# ce2.net
KiCad netlist of a schematic drawn in EAGLE
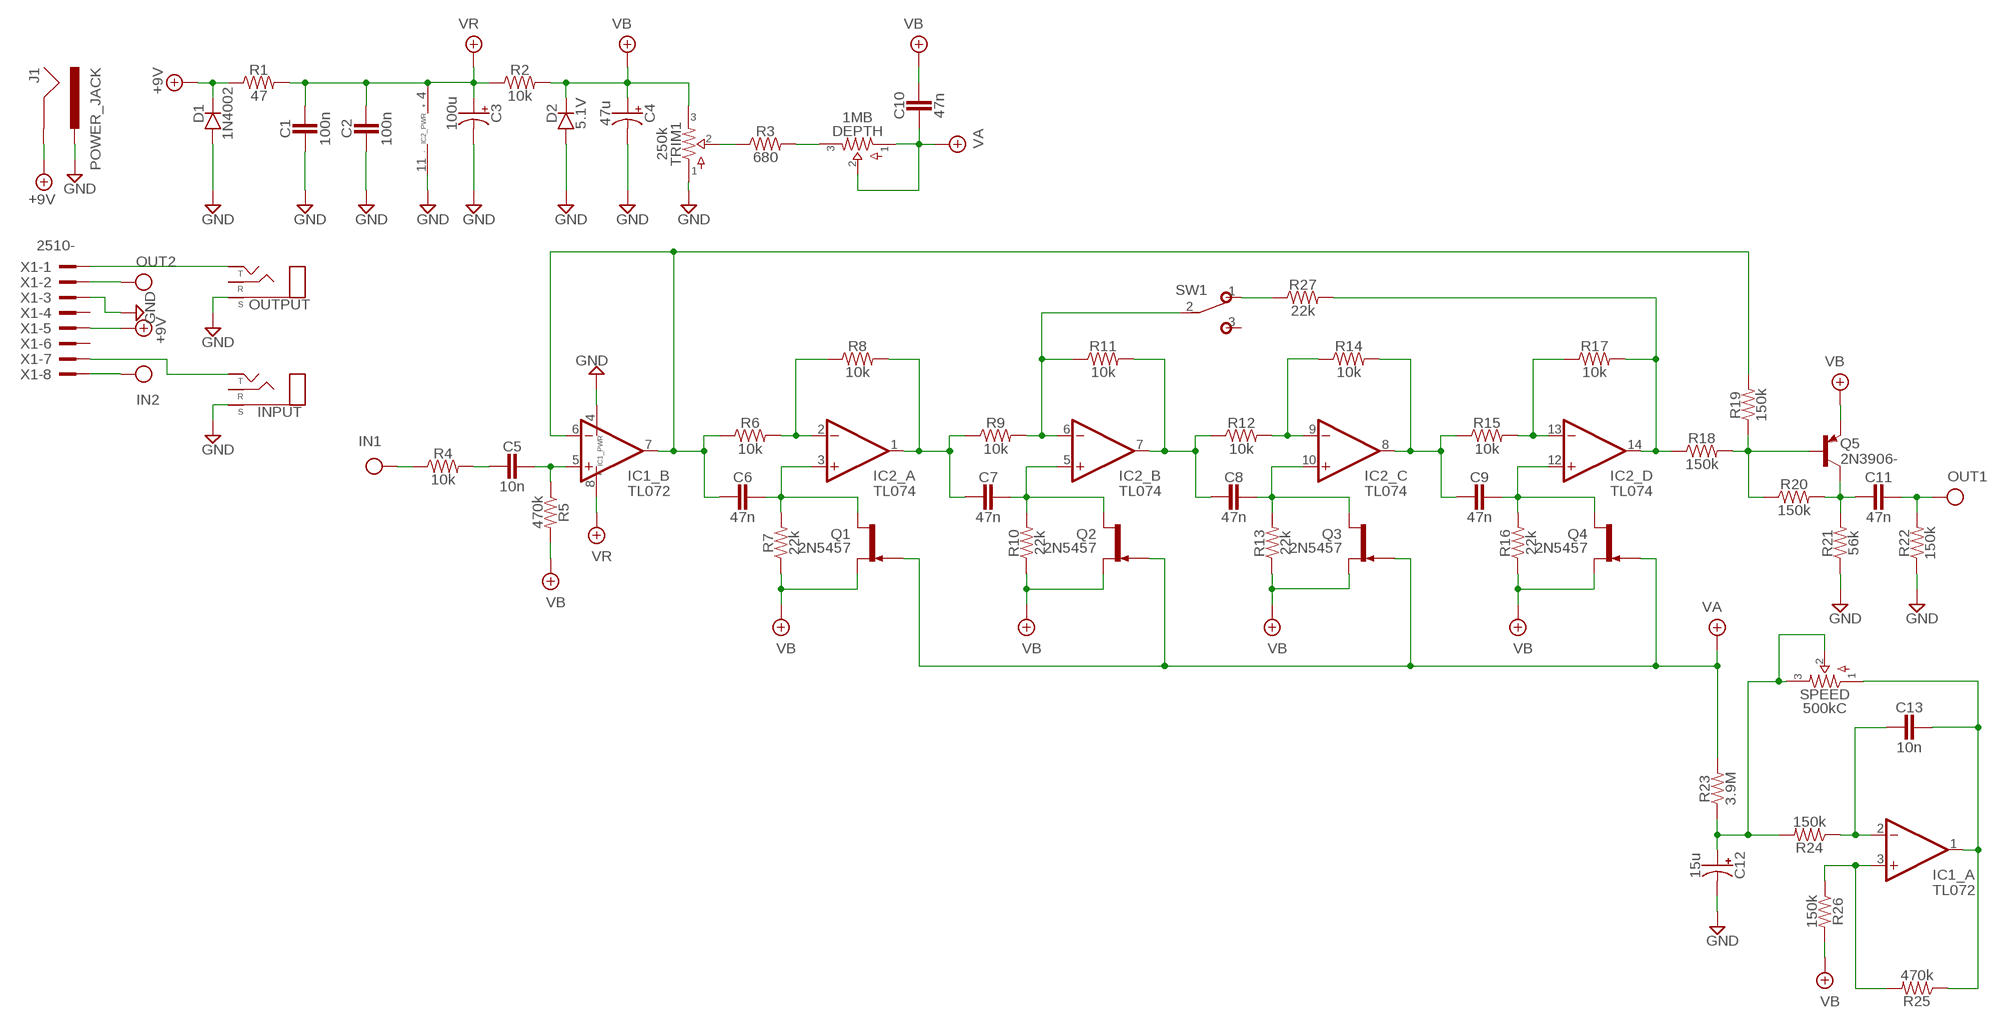
[diagram p0: schematic, sheet 1]

(export (version "E")
  (design (tool "Eeschema 10.0.6"))
  (components
    (comp (ref "C1")
      (value "100n")
      (footprint "eagle-import:050X030_025_2")
      (libsource (lib "eagle-import") (part "CER/FILM2"))
    )
    (comp (ref "C2")
      (value "100n")
      (footprint "eagle-import:050X030_025_2")
      (libsource (lib "eagle-import") (part "CER/FILM2"))
    )
    (comp (ref "C3")
      (value "100u")
      (footprint "eagle-import:050_020")
      (libsource (lib "eagle-import") (part "0500"))
    )
    (comp (ref "C4")
      (value "47u")
      (footprint "eagle-import:050_020")
      (libsource (lib "eagle-import") (part "0500"))
    )
    (comp (ref "C5")
      (value "10n")
      (footprint "eagle-import:BOX_SMALL")
      (libsource (lib "eagle-import") (part "CER/FILMBOX.1"))
    )
    (comp (ref "C6")
      (value "47n")
      (footprint "eagle-import:BOX_SMALL")
      (libsource (lib "eagle-import") (part "CER/FILMBOX.1"))
    )
    (comp (ref "C7")
      (value "47n")
      (footprint "eagle-import:BOX_SMALL")
      (libsource (lib "eagle-import") (part "CER/FILMBOX.1"))
    )
    (comp (ref "C8")
      (value "47n")
      (footprint "eagle-import:BOX_SMALL")
      (libsource (lib "eagle-import") (part "CER/FILMBOX.1"))
    )
    (comp (ref "C9")
      (value "47n")
      (footprint "eagle-import:BOX_SMALL")
      (libsource (lib "eagle-import") (part "CER/FILMBOX.1"))
    )
    (comp (ref "C10")
      (value "47n")
      (footprint "eagle-import:BOX_SMALL")
      (libsource (lib "eagle-import") (part "CER/FILMBOX.1"))
    )
    (comp (ref "C11")
      (value "47n")
      (footprint "eagle-import:BOX_SMALL")
      (libsource (lib "eagle-import") (part "CER/FILMBOX.1"))
    )
    (comp (ref "C12")
      (value "15u")
      (footprint "eagle-import:050_020_1")
      (libsource (lib "eagle-import") (part "0501"))
    )
    (comp (ref "C13")
      (value "10n")
      (footprint "eagle-import:BOX_SMALL")
      (libsource (lib "eagle-import") (part "CER/FILMBOX.1"))
    )
    (comp (ref "D1")
      (value "1N4002")
      (footprint "eagle-import:DO41-2")
      (libsource (lib "eagle-import") (part "DO41.2"))
    )
    (comp (ref "D2")
      (value "5.1V")
      (footprint "eagle-import:DO41-2")
      (libsource (lib "eagle-import") (part "DO41.2"))
    )
    (comp (ref "DEPTH")
      (value "1MB")
      (footprint "eagle-import:16MM")
      (libsource (lib "eagle-import") (part "POTS16MM"))
    )
    (comp (ref "IC1")
      (value "TL072")
      (footprint "eagle-import:DIL0")
      (libsource (lib "eagle-import") (part "DUALTH"))
    )
    (comp (ref "IC2")
      (value "TL074")
      (footprint "eagle-import:DIL14")
      (libsource (lib "eagle-import") (part "QUADTH"))
    )
    (comp (ref "INPUT")
      (value "STEREONMJ")
      (footprint "eagle-import:NMJ6HCD2")
      (libsource (lib "eagle-import") (part "STEREONMJ"))
    )
    (comp (ref "J1")
      (value "POWER_JACK")
      (footprint "eagle-import:POWER_JACK_PTH")
      (libsource (lib "eagle-import") (part "POWER_JACK"))
    )
    (comp (ref "OUTPUT")
      (value "STEREONMJ")
      (footprint "eagle-import:NMJ6HCD2")
      (libsource (lib "eagle-import") (part "STEREONMJ"))
    )
    (comp (ref "Q1")
      (value "2N5457")
      (footprint "eagle-import:TO92-")
      (libsource (lib "eagle-import") (part "2N5457"))
    )
    (comp (ref "Q2")
      (value "2N5457")
      (footprint "eagle-import:TO92-")
      (libsource (lib "eagle-import") (part "2N5457"))
    )
    (comp (ref "Q3")
      (value "2N5457")
      (footprint "eagle-import:TO92-")
      (libsource (lib "eagle-import") (part "2N5457"))
    )
    (comp (ref "Q4")
      (value "2N5457")
      (footprint "eagle-import:TO92-")
      (libsource (lib "eagle-import") (part "2N5457"))
    )
    (comp (ref "Q5")
      (value "2N3906-")
      (footprint "eagle-import:TO92-")
      (libsource (lib "eagle-import") (part "2N3906-"))
    )
    (comp (ref "R1")
      (value "47")
      (footprint "eagle-import:R0207_3")
      (libsource (lib "eagle-import") (part "R_.3B"))
    )
    (comp (ref "R2")
      (value "10k")
      (footprint "eagle-import:R0207_3")
      (libsource (lib "eagle-import") (part "R_.3B"))
    )
    (comp (ref "R3")
      (value "680")
      (footprint "eagle-import:R0207_3")
      (libsource (lib "eagle-import") (part "R_.3B"))
    )
    (comp (ref "R4")
      (value "10k")
      (footprint "eagle-import:R0207_3")
      (libsource (lib "eagle-import") (part "R_.3B"))
    )
    (comp (ref "R5")
      (value "470k")
      (footprint "eagle-import:R0207_3")
      (libsource (lib "eagle-import") (part "R_.3B"))
    )
    (comp (ref "R6")
      (value "10k")
      (footprint "eagle-import:R0207_3")
      (libsource (lib "eagle-import") (part "R_.3B"))
    )
    (comp (ref "R7")
      (value "22k")
      (footprint "eagle-import:R0207_3")
      (libsource (lib "eagle-import") (part "R_.3B"))
    )
    (comp (ref "R8")
      (value "10k")
      (footprint "eagle-import:R0207_3")
      (libsource (lib "eagle-import") (part "R_.3B"))
    )
    (comp (ref "R9")
      (value "10k")
      (footprint "eagle-import:R0207_3")
      (libsource (lib "eagle-import") (part "R_.3B"))
    )
    (comp (ref "R10")
      (value "22k")
      (footprint "eagle-import:R0207_3")
      (libsource (lib "eagle-import") (part "R_.3B"))
    )
    (comp (ref "R11")
      (value "10k")
      (footprint "eagle-import:R0207_3")
      (libsource (lib "eagle-import") (part "R_.3B"))
    )
    (comp (ref "R12")
      (value "10k")
      (footprint "eagle-import:R0207_3")
      (libsource (lib "eagle-import") (part "R_.3B"))
    )
    (comp (ref "R13")
      (value "22k")
      (footprint "eagle-import:R0207_3")
      (libsource (lib "eagle-import") (part "R_.3B"))
    )
    (comp (ref "R14")
      (value "10k")
      (footprint "eagle-import:R0207_3")
      (libsource (lib "eagle-import") (part "R_.3B"))
    )
    (comp (ref "R15")
      (value "10k")
      (footprint "eagle-import:R0207_3")
      (libsource (lib "eagle-import") (part "R_.3B"))
    )
    (comp (ref "R16")
      (value "22k")
      (footprint "eagle-import:R0207_3")
      (libsource (lib "eagle-import") (part "R_.3B"))
    )
    (comp (ref "R17")
      (value "10k")
      (footprint "eagle-import:R0207_3")
      (libsource (lib "eagle-import") (part "R_.3B"))
    )
    (comp (ref "R18")
      (value "150k")
      (footprint "eagle-import:R0207_3")
      (libsource (lib "eagle-import") (part "R_.3B"))
    )
    (comp (ref "R19")
      (value "150k")
      (footprint "eagle-import:R0207_3")
      (libsource (lib "eagle-import") (part "R_.3B"))
    )
    (comp (ref "R20")
      (value "150k")
      (footprint "eagle-import:R0207_3")
      (libsource (lib "eagle-import") (part "R_.3B"))
    )
    (comp (ref "R21")
      (value "56k")
      (footprint "eagle-import:R0207_3")
      (libsource (lib "eagle-import") (part "R_.3B"))
    )
    (comp (ref "R22")
      (value "150k")
      (footprint "eagle-import:R0207_3")
      (libsource (lib "eagle-import") (part "R_.3B"))
    )
    (comp (ref "R23")
      (value "3.9M")
      (footprint "eagle-import:R0207_3")
      (libsource (lib "eagle-import") (part "R_.3B"))
    )
    (comp (ref "R24")
      (value "150k")
      (footprint "eagle-import:R0207_3")
      (libsource (lib "eagle-import") (part "R_.3B"))
    )
    (comp (ref "R25")
      (value "470k")
      (footprint "eagle-import:R0207_3")
      (libsource (lib "eagle-import") (part "R_.3B"))
    )
    (comp (ref "R26")
      (value "150k")
      (footprint "eagle-import:R0207_3")
      (libsource (lib "eagle-import") (part "R_.3B"))
    )
    (comp (ref "R27")
      (value "22k")
      (footprint "eagle-import:R0207_3")
      (libsource (lib "eagle-import") (part "R_.3B"))
    )
    (comp (ref "SPEED")
      (value "500kC")
      (footprint "eagle-import:16MM")
      (libsource (lib "eagle-import") (part "POTS16MM"))
    )
    (comp (ref "SW1")
      (value "SPDTPIN_MOUNT")
      (footprint "eagle-import:1MS1T1B1C0M2QE")
      (libsource (lib "eagle-import") (part "SPDTPIN_MOUNT"))
    )
    (comp (ref "TRIM1")
      (value "250k")
      (footprint "eagle-import:RTRIM3296W")
      (libsource (lib "eagle-import") (part "POTSTEST"))
    )
    (comp (ref "X1")
      (value "2510-")
      (footprint "eagle-import:PAK100_2500-10")
      (fields (field (name "MF") "3M") (field (name "MPN") "2510-6002UB"))
      (libsource (lib "eagle-import") (part "2510-"))
    )
  )
  (nets
    (net (code "1") (name "+9V") (class "Default")
      (node (ref "D1") (pin "C") (pinfunction "C_C") (pintype "passive"))
      (node (ref "J1") (pin "GND") (pinfunction "GND_GND") (pintype "bidirectional"))
      (node (ref "R1") (pin "1") (pinfunction "1_1") (pintype "passive"))
      (node (ref "X1") (pin "5") (pinfunction "KL_5") (pintype "passive"))
    )
    (net (code "2") (name "GND") (class "Default")
      (node (ref "C1") (pin "2") (pinfunction "2_2") (pintype "passive"))
      (node (ref "C12") (pin "-") (pinfunction "-_-") (pintype "passive"))
      (node (ref "C2") (pin "2") (pinfunction "2_2") (pintype "passive"))
      (node (ref "C3") (pin "-") (pinfunction "-_-") (pintype "passive"))
      (node (ref "C4") (pin "-") (pinfunction "-_-") (pintype "passive"))
      (node (ref "D1") (pin "A") (pinfunction "A_A") (pintype "passive"))
      (node (ref "D2") (pin "A") (pinfunction "A_A") (pintype "passive"))
      (node (ref "IC1") (pin "4") (pinfunction "V-_4") (pintype "power_in"))
      (node (ref "IC2") (pin "11") (pinfunction "V-_11") (pintype "power_in"))
      (node (ref "INPUT") (pin "S") (pinfunction "S_S") (pintype "passive"))
      (node (ref "J1") (pin "PWR") (pinfunction "PWR_PWR") (pintype "bidirectional"))
      (node (ref "OUTPUT") (pin "S") (pinfunction "S_S") (pintype "passive"))
      (node (ref "R21") (pin "1") (pinfunction "1_1") (pintype "passive"))
      (node (ref "R22") (pin "1") (pinfunction "1_1") (pintype "passive"))
      (node (ref "TRIM1") (pin "1") (pinfunction "1_1") (pintype "passive"))
      (node (ref "X1") (pin "3") (pinfunction "KL_3") (pintype "passive"))
    )
    (net (code "3") (name "IN") (class "Default")
      (node (ref "R4") (pin "1") (pinfunction "1_1") (pintype "passive"))
      (node (ref "X1") (pin "8") (pinfunction "KL_8") (pintype "passive"))
    )
    (net (code "4") (name "Net-(C5-Pad2)") (class "Default")
      (node (ref "C5") (pin "2") (pinfunction "2_2") (pintype "passive"))
      (node (ref "R4") (pin "2") (pinfunction "2_2") (pintype "passive"))
    )
    (net (code "5") (name "Net-(C12-Pad+)") (class "Default")
      (node (ref "C12") (pin "+") (pinfunction "+_+") (pintype "passive"))
      (node (ref "R23") (pin "1") (pinfunction "1_1") (pintype "passive"))
      (node (ref "R24") (pin "2") (pinfunction "2_2") (pintype "passive"))
      (node (ref "SPEED") (pin "2") (pinfunction "2_2") (pintype "passive"))
      (node (ref "SPEED") (pin "3") (pinfunction "3_3") (pintype "passive"))
    )
    (net (code "6") (name "Net-(DEPTH-Pad3)") (class "Default")
      (node (ref "DEPTH") (pin "3") (pinfunction "3_3") (pintype "passive"))
      (node (ref "R3") (pin "2") (pinfunction "2_2") (pintype "passive"))
    )
    (net (code "7") (name "Net-(IC1A-+IN)") (class "Default")
      (node (ref "IC1") (pin "3") (pinfunction "+IN_3") (pintype "input"))
      (node (ref "R25") (pin "2") (pinfunction "2_2") (pintype "passive"))
      (node (ref "R26") (pin "1") (pinfunction "1_1") (pintype "passive"))
    )
    (net (code "8") (name "Net-(IC1A--IN)") (class "Default")
      (node (ref "C13") (pin "2") (pinfunction "2_2") (pintype "passive"))
      (node (ref "IC1") (pin "2") (pinfunction "-IN_2") (pintype "input"))
      (node (ref "R24") (pin "1") (pinfunction "1_1") (pintype "passive"))
    )
    (net (code "9") (name "Net-(IC1A-OUT)") (class "Default")
      (node (ref "C13") (pin "1") (pinfunction "1_1") (pintype "passive"))
      (node (ref "IC1") (pin "1") (pinfunction "OUT_1") (pintype "output"))
      (node (ref "R25") (pin "1") (pinfunction "1_1") (pintype "passive"))
      (node (ref "SPEED") (pin "1") (pinfunction "1_1") (pintype "passive"))
    )
    (net (code "10") (name "Net-(IC1B-+IN)") (class "Default")
      (node (ref "C5") (pin "1") (pinfunction "1_1") (pintype "passive"))
      (node (ref "IC1") (pin "5") (pinfunction "+IN_5") (pintype "input"))
      (node (ref "R5") (pin "1") (pinfunction "1_1") (pintype "passive"))
    )
    (net (code "11") (name "Net-(IC1B--IN)") (class "Default")
      (node (ref "C6") (pin "2") (pinfunction "2_2") (pintype "passive"))
      (node (ref "IC1") (pin "6") (pinfunction "-IN_6") (pintype "input"))
      (node (ref "IC1") (pin "7") (pinfunction "OUT_7") (pintype "output"))
      (node (ref "R19") (pin "2") (pinfunction "2_2") (pintype "passive"))
      (node (ref "R6") (pin "1") (pinfunction "1_1") (pintype "passive"))
    )
    (net (code "12") (name "Net-(IC2A-+IN)") (class "Default")
      (node (ref "C6") (pin "1") (pinfunction "1_1") (pintype "passive"))
      (node (ref "IC2") (pin "3") (pinfunction "+IN_3") (pintype "input"))
      (node (ref "Q1") (pin "3") (pinfunction "D_3") (pintype "passive"))
      (node (ref "R7") (pin "2") (pinfunction "2_2") (pintype "passive"))
    )
    (net (code "13") (name "Net-(IC2A--IN)") (class "Default")
      (node (ref "IC2") (pin "2") (pinfunction "-IN_2") (pintype "input"))
      (node (ref "R6") (pin "2") (pinfunction "2_2") (pintype "passive"))
      (node (ref "R8") (pin "1") (pinfunction "1_1") (pintype "passive"))
    )
    (net (code "14") (name "Net-(IC2A-OUT)") (class "Default")
      (node (ref "C7") (pin "2") (pinfunction "2_2") (pintype "passive"))
      (node (ref "IC2") (pin "1") (pinfunction "OUT_1") (pintype "output"))
      (node (ref "R8") (pin "2") (pinfunction "2_2") (pintype "passive"))
      (node (ref "R9") (pin "1") (pinfunction "1_1") (pintype "passive"))
    )
    (net (code "15") (name "Net-(IC2B-+IN)") (class "Default")
      (node (ref "C7") (pin "1") (pinfunction "1_1") (pintype "passive"))
      (node (ref "IC2") (pin "5") (pinfunction "+IN_5") (pintype "input"))
      (node (ref "Q2") (pin "3") (pinfunction "D_3") (pintype "passive"))
      (node (ref "R10") (pin "2") (pinfunction "2_2") (pintype "passive"))
    )
    (net (code "16") (name "Net-(IC2B--IN)") (class "Default")
      (node (ref "IC2") (pin "6") (pinfunction "-IN_6") (pintype "input"))
      (node (ref "R11") (pin "1") (pinfunction "1_1") (pintype "passive"))
      (node (ref "R9") (pin "2") (pinfunction "2_2") (pintype "passive"))
      (node (ref "SW1") (pin "2") (pinfunction "P_2") (pintype "passive"))
    )
    (net (code "17") (name "Net-(IC2B-OUT)") (class "Default")
      (node (ref "C8") (pin "2") (pinfunction "2_2") (pintype "passive"))
      (node (ref "IC2") (pin "7") (pinfunction "OUT_7") (pintype "output"))
      (node (ref "R11") (pin "2") (pinfunction "2_2") (pintype "passive"))
      (node (ref "R12") (pin "1") (pinfunction "1_1") (pintype "passive"))
    )
    (net (code "18") (name "Net-(IC2C-+IN)") (class "Default")
      (node (ref "C8") (pin "1") (pinfunction "1_1") (pintype "passive"))
      (node (ref "IC2") (pin "10") (pinfunction "+IN_10") (pintype "input"))
      (node (ref "Q3") (pin "3") (pinfunction "D_3") (pintype "passive"))
      (node (ref "R13") (pin "2") (pinfunction "2_2") (pintype "passive"))
    )
    (net (code "19") (name "Net-(IC2C--IN)") (class "Default")
      (node (ref "IC2") (pin "9") (pinfunction "-IN_9") (pintype "input"))
      (node (ref "R12") (pin "2") (pinfunction "2_2") (pintype "passive"))
      (node (ref "R14") (pin "1") (pinfunction "1_1") (pintype "passive"))
    )
    (net (code "20") (name "Net-(IC2C-OUT)") (class "Default")
      (node (ref "C9") (pin "2") (pinfunction "2_2") (pintype "passive"))
      (node (ref "IC2") (pin "8") (pinfunction "OUT_8") (pintype "output"))
      (node (ref "R14") (pin "2") (pinfunction "2_2") (pintype "passive"))
      (node (ref "R15") (pin "1") (pinfunction "1_1") (pintype "passive"))
    )
    (net (code "21") (name "Net-(IC2D-+IN)") (class "Default")
      (node (ref "C9") (pin "1") (pinfunction "1_1") (pintype "passive"))
      (node (ref "IC2") (pin "12") (pinfunction "+IN_12") (pintype "input"))
      (node (ref "Q4") (pin "3") (pinfunction "D_3") (pintype "passive"))
      (node (ref "R16") (pin "2") (pinfunction "2_2") (pintype "passive"))
    )
    (net (code "22") (name "Net-(IC2D--IN)") (class "Default")
      (node (ref "IC2") (pin "13") (pinfunction "-IN_13") (pintype "input"))
      (node (ref "R15") (pin "2") (pinfunction "2_2") (pintype "passive"))
      (node (ref "R17") (pin "1") (pinfunction "1_1") (pintype "passive"))
    )
    (net (code "23") (name "Net-(IC2D-OUT)") (class "Default")
      (node (ref "IC2") (pin "14") (pinfunction "OUT_14") (pintype "output"))
      (node (ref "R17") (pin "2") (pinfunction "2_2") (pintype "passive"))
      (node (ref "R18") (pin "1") (pinfunction "1_1") (pintype "passive"))
      (node (ref "R27") (pin "2") (pinfunction "2_2") (pintype "passive"))
    )
    (net (code "24") (name "Net-(Q5-B)") (class "Default")
      (node (ref "Q5") (pin "2") (pinfunction "B_2") (pintype "passive"))
      (node (ref "R18") (pin "2") (pinfunction "2_2") (pintype "passive"))
      (node (ref "R19") (pin "1") (pinfunction "1_1") (pintype "passive"))
      (node (ref "R20") (pin "1") (pinfunction "1_1") (pintype "passive"))
    )
    (net (code "25") (name "Net-(Q5-C)") (class "Default")
      (node (ref "C11") (pin "2") (pinfunction "2_2") (pintype "passive"))
      (node (ref "Q5") (pin "1") (pinfunction "C_1") (pintype "passive"))
      (node (ref "R20") (pin "2") (pinfunction "2_2") (pintype "passive"))
      (node (ref "R21") (pin "2") (pinfunction "2_2") (pintype "passive"))
    )
    (net (code "26") (name "Net-(R3-Pad1)") (class "Default")
      (node (ref "R3") (pin "1") (pinfunction "1_1") (pintype "passive"))
      (node (ref "TRIM1") (pin "2") (pinfunction "2_2") (pintype "passive"))
    )
    (net (code "27") (name "Net-(SW1-O)") (class "Default")
      (node (ref "R27") (pin "1") (pinfunction "1_1") (pintype "passive"))
      (node (ref "SW1") (pin "1") (pinfunction "O_1") (pintype "passive"))
    )
    (net (code "28") (name "Net-(X1A-KL)") (class "Default")
      (node (ref "OUTPUT") (pin "T") (pinfunction "T_T") (pintype "passive"))
      (node (ref "X1") (pin "1") (pinfunction "KL_1") (pintype "passive"))
    )
    (net (code "29") (name "Net-(X1G-KL)") (class "Default")
      (node (ref "INPUT") (pin "T") (pinfunction "T_T") (pintype "passive"))
      (node (ref "X1") (pin "7") (pinfunction "KL_7") (pintype "passive"))
    )
    (net (code "30") (name "OUT") (class "Default")
      (node (ref "C11") (pin "1") (pinfunction "1_1") (pintype "passive"))
      (node (ref "R22") (pin "2") (pinfunction "2_2") (pintype "passive"))
      (node (ref "X1") (pin "2") (pinfunction "KL_2") (pintype "passive"))
    )
    (net (code "31") (name "VA") (class "Default")
      (node (ref "C10") (pin "2") (pinfunction "2_2") (pintype "passive"))
      (node (ref "DEPTH") (pin "1") (pinfunction "1_1") (pintype "passive"))
      (node (ref "DEPTH") (pin "2") (pinfunction "2_2") (pintype "passive"))
      (node (ref "Q1") (pin "1") (pinfunction "G_1") (pintype "passive"))
      (node (ref "Q2") (pin "1") (pinfunction "G_1") (pintype "passive"))
      (node (ref "Q3") (pin "1") (pinfunction "G_1") (pintype "passive"))
      (node (ref "Q4") (pin "1") (pinfunction "G_1") (pintype "passive"))
      (node (ref "R23") (pin "2") (pinfunction "2_2") (pintype "passive"))
    )
    (net (code "32") (name "VB") (class "Default")
      (node (ref "C10") (pin "1") (pinfunction "1_1") (pintype "passive"))
      (node (ref "C4") (pin "+") (pinfunction "+_+") (pintype "passive"))
      (node (ref "D2") (pin "C") (pinfunction "C_C") (pintype "passive"))
      (node (ref "Q1") (pin "2") (pinfunction "S_2") (pintype "passive"))
      (node (ref "Q2") (pin "2") (pinfunction "S_2") (pintype "passive"))
      (node (ref "Q3") (pin "2") (pinfunction "S_2") (pintype "passive"))
      (node (ref "Q4") (pin "2") (pinfunction "S_2") (pintype "passive"))
      (node (ref "Q5") (pin "3") (pinfunction "E_3") (pintype "passive"))
      (node (ref "R10") (pin "1") (pinfunction "1_1") (pintype "passive"))
      (node (ref "R13") (pin "1") (pinfunction "1_1") (pintype "passive"))
      (node (ref "R16") (pin "1") (pinfunction "1_1") (pintype "passive"))
      (node (ref "R2") (pin "2") (pinfunction "2_2") (pintype "passive"))
      (node (ref "R26") (pin "2") (pinfunction "2_2") (pintype "passive"))
      (node (ref "R5") (pin "2") (pinfunction "2_2") (pintype "passive"))
      (node (ref "R7") (pin "1") (pinfunction "1_1") (pintype "passive"))
      (node (ref "TRIM1") (pin "3") (pinfunction "3_3") (pintype "passive"))
    )
    (net (code "33") (name "VR") (class "Default")
      (node (ref "C1") (pin "1") (pinfunction "1_1") (pintype "passive"))
      (node (ref "C2") (pin "1") (pinfunction "1_1") (pintype "passive"))
      (node (ref "C3") (pin "+") (pinfunction "+_+") (pintype "passive"))
      (node (ref "IC1") (pin "8") (pinfunction "V+_8") (pintype "power_in"))
      (node (ref "IC2") (pin "4") (pinfunction "V+_4") (pintype "power_in"))
      (node (ref "R1") (pin "2") (pinfunction "2_2") (pintype "passive"))
      (node (ref "R2") (pin "1") (pinfunction "1_1") (pintype "passive"))
    )
    (net (code "34") (name "unconnected-(INPUT-PadR)") (class "Default")
      (node (ref "INPUT") (pin "R") (pinfunction "R_R") (pintype "passive"))
    )
    (net (code "35") (name "unconnected-(OUTPUT-PadR)") (class "Default")
      (node (ref "OUTPUT") (pin "R") (pinfunction "R_R") (pintype "passive"))
    )
    (net (code "36") (name "unconnected-(SW1-S-Pad3)") (class "Default")
      (node (ref "SW1") (pin "3") (pinfunction "S_3") (pintype "passive"))
    )
    (net (code "37") (name "unconnected-(X1D-KL-Pad4)") (class "Default")
      (node (ref "X1") (pin "4") (pinfunction "KL_4") (pintype "passive"))
    )
    (net (code "38") (name "unconnected-(X1F-KL-Pad6)") (class "Default")
      (node (ref "X1") (pin "6") (pinfunction "KL_6") (pintype "passive"))
    )
  )
)
